# out_matrix.net
KiCad netlist of a schematic drawn in EAGLE
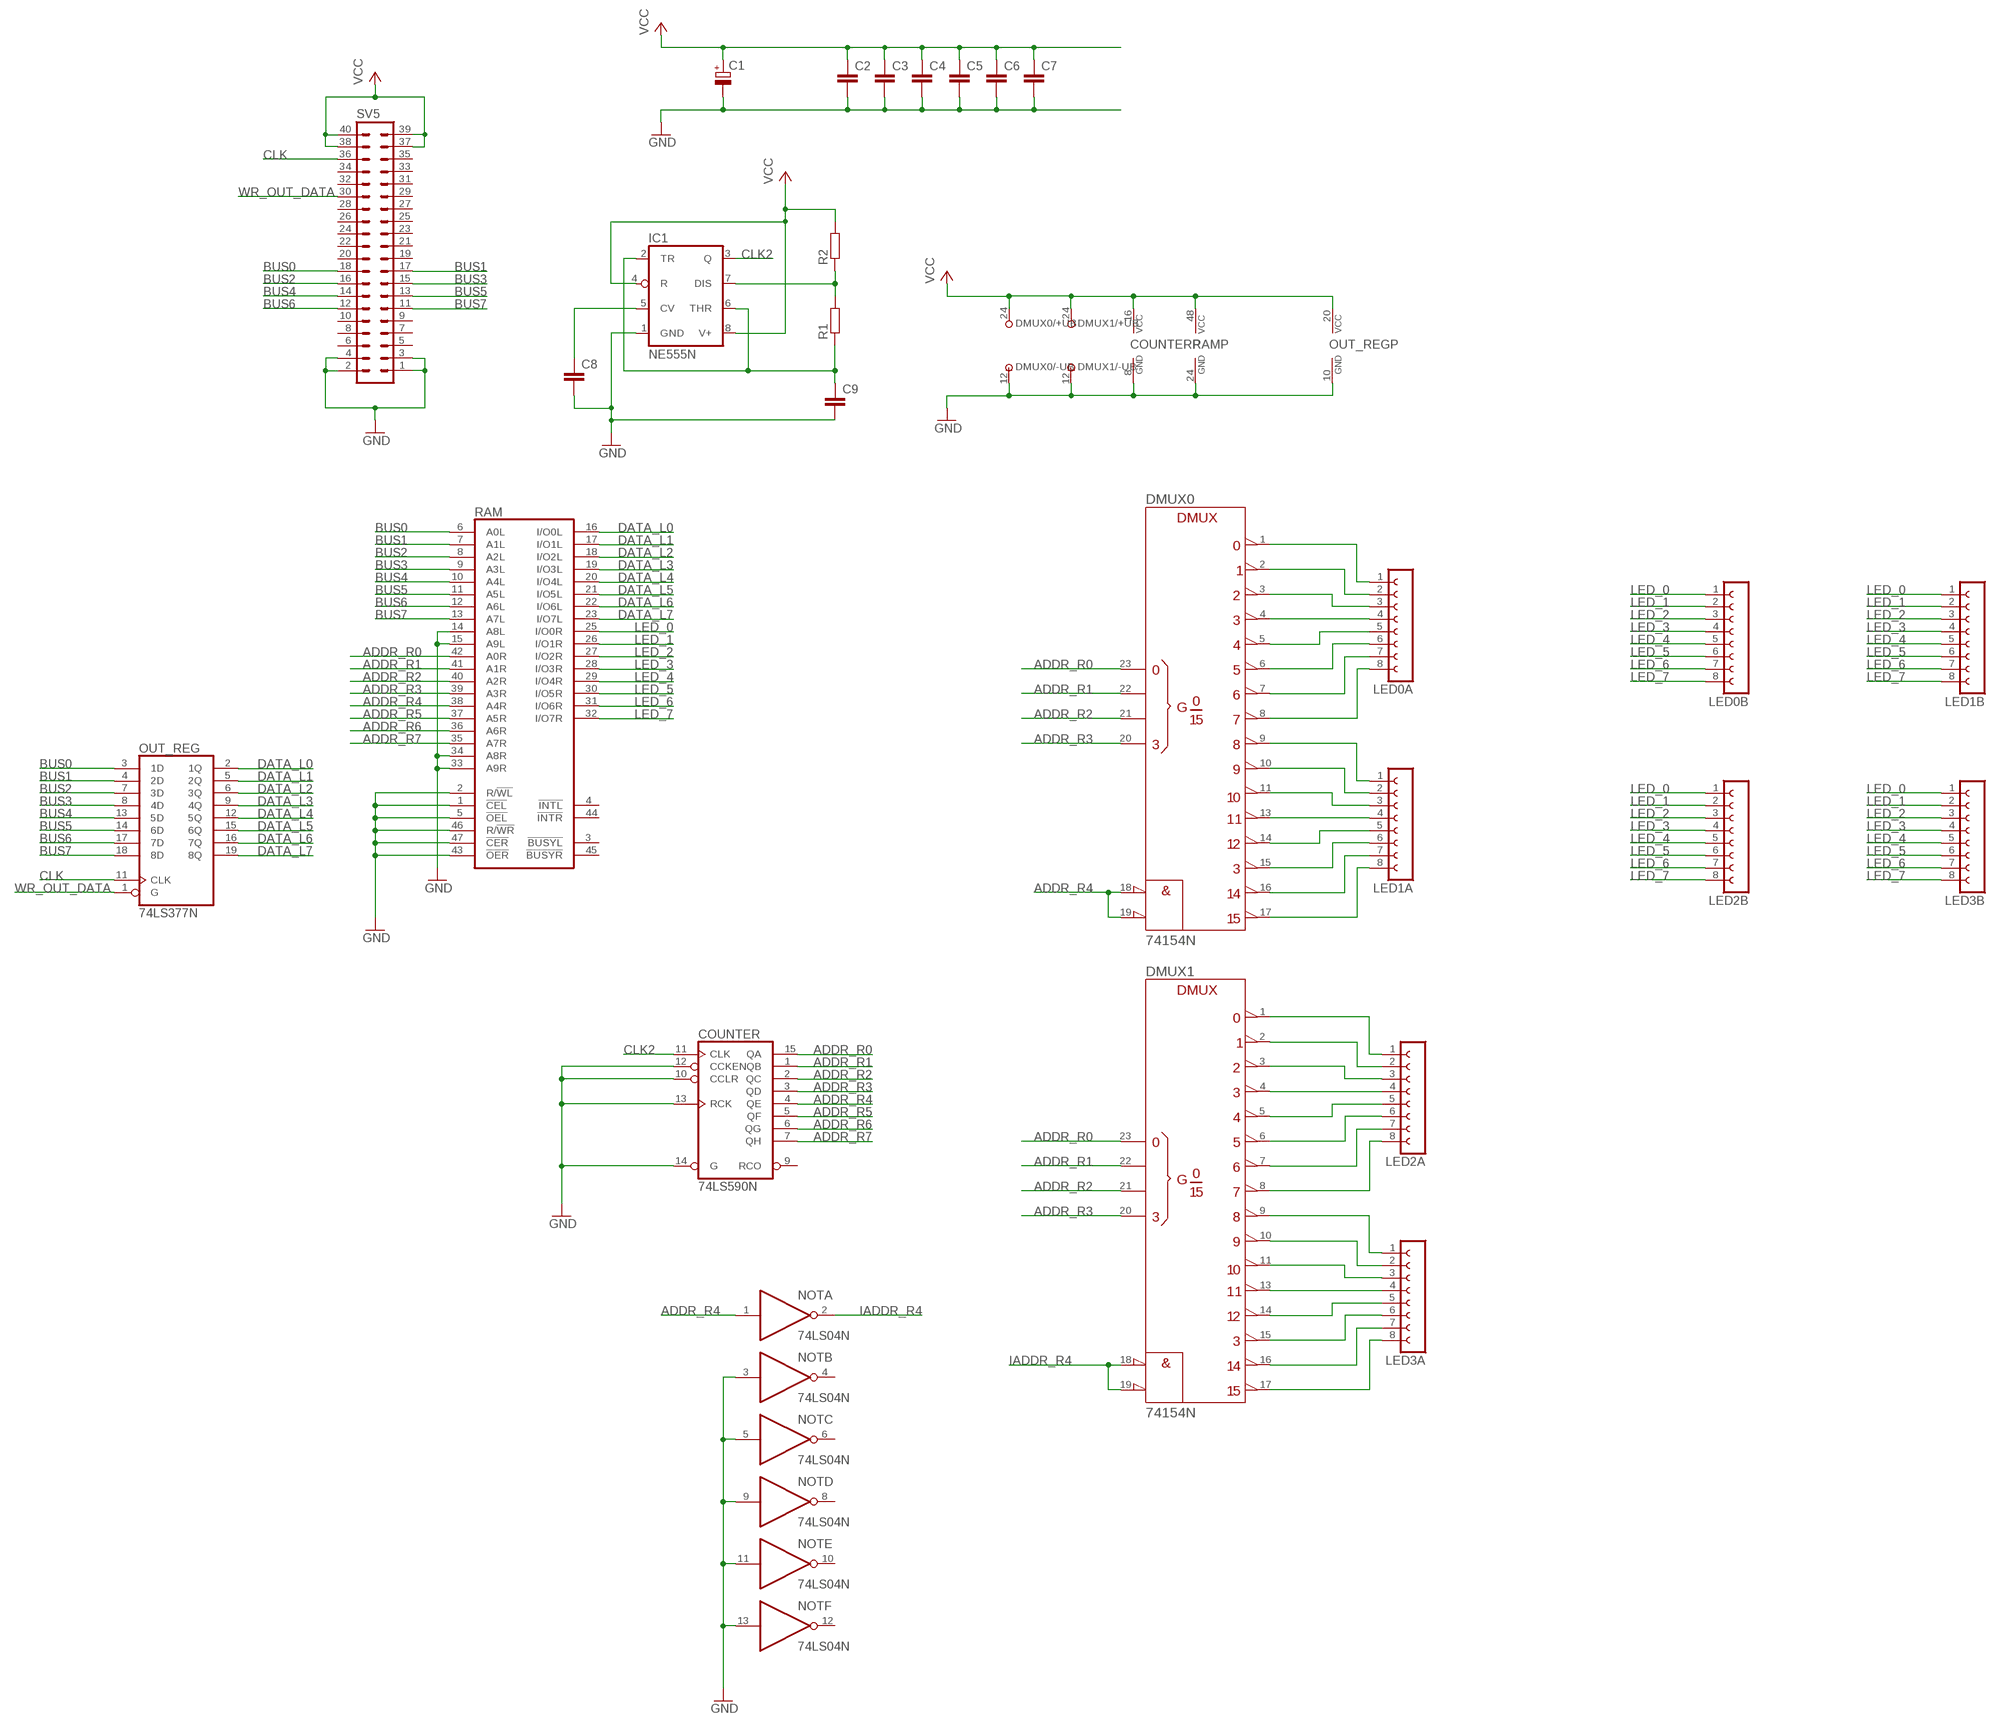
[diagram p0: schematic, sheet 1]

(export (version "E")
  (design (tool "Eeschema 10.0.6"))
  (components
    (comp (ref "C1")
      (value "CPOL-EUE3.5-8")
      (footprint "eagle-import:E3,5-8")
      (libsource (lib "eagle-import") (part "CPOL-EUE3.5-8"))
    )
    (comp (ref "C2")
      (value "C-EUC1206K")
      (footprint "eagle-import:C1206K")
      (libsource (lib "eagle-import") (part "C-EUC1206K"))
    )
    (comp (ref "C3")
      (value "C-EUC1206K")
      (footprint "eagle-import:C1206K")
      (libsource (lib "eagle-import") (part "C-EUC1206K"))
    )
    (comp (ref "C4")
      (value "C-EUC1206K")
      (footprint "eagle-import:C1206K")
      (libsource (lib "eagle-import") (part "C-EUC1206K"))
    )
    (comp (ref "C5")
      (value "C-EUC1206K")
      (footprint "eagle-import:C1206K")
      (libsource (lib "eagle-import") (part "C-EUC1206K"))
    )
    (comp (ref "C6")
      (value "C-EUC1206K")
      (footprint "eagle-import:C1206K")
      (libsource (lib "eagle-import") (part "C-EUC1206K"))
    )
    (comp (ref "C7")
      (value "C-EUC1206K")
      (footprint "eagle-import:C1206K")
      (libsource (lib "eagle-import") (part "C-EUC1206K"))
    )
    (comp (ref "C8")
      (value "C-EUC1206K")
      (footprint "eagle-import:C1206K")
      (libsource (lib "eagle-import") (part "C-EUC1206K"))
    )
    (comp (ref "C9")
      (value "C-EUC1206K")
      (footprint "eagle-import:C1206K")
      (libsource (lib "eagle-import") (part "C-EUC1206K"))
    )
    (comp (ref "COUNTER")
      (value "74LS590N")
      (footprint "eagle-import:DIL16")
      (libsource (lib "eagle-import") (part "74590NLS"))
    )
    (comp (ref "DMUX0")
      (value "74154N")
      (footprint "eagle-import:DIL24-3")
      (libsource (lib "eagle-import") (part "74154N"))
    )
    (comp (ref "DMUX1")
      (value "74154N")
      (footprint "eagle-import:DIL24-3")
      (libsource (lib "eagle-import") (part "74154N"))
    )
    (comp (ref "IC1")
      (value "NE555N")
      (footprint "eagle-import:DIL08")
      (libsource (lib "eagle-import") (part "555NNE"))
    )
    (comp (ref "LED0A")
      (value "FE08-1")
      (footprint "eagle-import:FE08")
      (libsource (lib "eagle-import") (part "FE08-1"))
    )
    (comp (ref "LED0B")
      (value "FE08-1")
      (footprint "eagle-import:FE08")
      (libsource (lib "eagle-import") (part "FE08-1"))
    )
    (comp (ref "LED1A")
      (value "FE08-1")
      (footprint "eagle-import:FE08")
      (libsource (lib "eagle-import") (part "FE08-1"))
    )
    (comp (ref "LED1B")
      (value "FE08-1")
      (footprint "eagle-import:FE08")
      (libsource (lib "eagle-import") (part "FE08-1"))
    )
    (comp (ref "LED2A")
      (value "FE08-1")
      (footprint "eagle-import:FE08")
      (libsource (lib "eagle-import") (part "FE08-1"))
    )
    (comp (ref "LED2B")
      (value "FE08-1")
      (footprint "eagle-import:FE08")
      (libsource (lib "eagle-import") (part "FE08-1"))
    )
    (comp (ref "LED3A")
      (value "FE08-1")
      (footprint "eagle-import:FE08")
      (libsource (lib "eagle-import") (part "FE08-1"))
    )
    (comp (ref "LED3B")
      (value "FE08-1")
      (footprint "eagle-import:FE08")
      (libsource (lib "eagle-import") (part "FE08-1"))
    )
    (comp (ref "NOT")
      (value "74LS04N")
      (footprint "eagle-import:DIL14")
      (libsource (lib "eagle-import") (part "7404NLS"))
    )
    (comp (ref "OUT_REG")
      (value "74LS377N")
      (footprint "eagle-import:DIL20")
      (libsource (lib "eagle-import") (part "74377NLS"))
    )
    (comp (ref "R1")
      (value "R-EU_M1206")
      (footprint "eagle-import:M1206")
      (libsource (lib "eagle-import") (part "R-EU_M1206"))
    )
    (comp (ref "R2")
      (value "R-EU_M1206")
      (footprint "eagle-import:M1206")
      (libsource (lib "eagle-import") (part "R-EU_M1206"))
    )
    (comp (ref "RAM")
      (value "7130P")
      (footprint "eagle-import:DIL48")
      (libsource (lib "eagle-import") (part "7130P"))
    )
    (comp (ref "SV5")
      (value "MA20-2W")
      (footprint "eagle-import:MA20-2W")
      (libsource (lib "eagle-import") (part "MA20-2W"))
    )
  )
  (nets
    (net (code "1") (name "/ADDR_R0") (class "Default")
      (node (ref "COUNTER") (pin "15") (pinfunction "QA_15") (pintype "tri_state"))
      (node (ref "DMUX0") (pin "23") (pinfunction "A_23") (pintype "input"))
      (node (ref "DMUX1") (pin "23") (pinfunction "A_23") (pintype "input"))
      (node (ref "RAM") (pin "42") (pinfunction "A0R_42") (pintype "input"))
    )
    (net (code "2") (name "/ADDR_R1") (class "Default")
      (node (ref "COUNTER") (pin "1") (pinfunction "QB_1") (pintype "tri_state"))
      (node (ref "DMUX0") (pin "22") (pinfunction "B_22") (pintype "input"))
      (node (ref "DMUX1") (pin "22") (pinfunction "B_22") (pintype "input"))
      (node (ref "RAM") (pin "41") (pinfunction "A1R_41") (pintype "input"))
    )
    (net (code "3") (name "/ADDR_R2") (class "Default")
      (node (ref "COUNTER") (pin "2") (pinfunction "QC_2") (pintype "tri_state"))
      (node (ref "DMUX0") (pin "21") (pinfunction "C_21") (pintype "input"))
      (node (ref "DMUX1") (pin "21") (pinfunction "C_21") (pintype "input"))
      (node (ref "RAM") (pin "40") (pinfunction "A2R_40") (pintype "input"))
    )
    (net (code "4") (name "/ADDR_R3") (class "Default")
      (node (ref "COUNTER") (pin "3") (pinfunction "QD_3") (pintype "tri_state"))
      (node (ref "DMUX0") (pin "20") (pinfunction "D_20") (pintype "input"))
      (node (ref "DMUX1") (pin "20") (pinfunction "D_20") (pintype "input"))
      (node (ref "RAM") (pin "39") (pinfunction "A3R_39") (pintype "input"))
    )
    (net (code "5") (name "/ADDR_R4") (class "Default")
      (node (ref "COUNTER") (pin "4") (pinfunction "QE_4") (pintype "tri_state"))
      (node (ref "DMUX0") (pin "18") (pinfunction "~{G1}_18") (pintype "input"))
      (node (ref "DMUX0") (pin "19") (pinfunction "~{G2}_19") (pintype "input"))
      (node (ref "NOT") (pin "1") (pinfunction "I_1") (pintype "input"))
      (node (ref "RAM") (pin "38") (pinfunction "A4R_38") (pintype "input"))
    )
    (net (code "6") (name "/ADDR_R5") (class "Default")
      (node (ref "COUNTER") (pin "5") (pinfunction "QF_5") (pintype "tri_state"))
      (node (ref "RAM") (pin "37") (pinfunction "A5R_37") (pintype "input"))
    )
    (net (code "7") (name "/ADDR_R6") (class "Default")
      (node (ref "COUNTER") (pin "6") (pinfunction "QG_6") (pintype "tri_state"))
      (node (ref "RAM") (pin "36") (pinfunction "A6R_36") (pintype "input"))
    )
    (net (code "8") (name "/ADDR_R7") (class "Default")
      (node (ref "COUNTER") (pin "7") (pinfunction "QH_7") (pintype "tri_state"))
      (node (ref "RAM") (pin "35") (pinfunction "A7R_35") (pintype "input"))
    )
    (net (code "9") (name "/BUS0") (class "Default")
      (node (ref "OUT_REG") (pin "3") (pinfunction "1D_3") (pintype "input"))
      (node (ref "RAM") (pin "6") (pinfunction "A0L_6") (pintype "input"))
      (node (ref "SV5") (pin "18") (pinfunction "18_18") (pintype "passive"))
    )
    (net (code "10") (name "/BUS1") (class "Default")
      (node (ref "OUT_REG") (pin "4") (pinfunction "2D_4") (pintype "input"))
      (node (ref "RAM") (pin "7") (pinfunction "A1L_7") (pintype "input"))
      (node (ref "SV5") (pin "17") (pinfunction "17_17") (pintype "passive"))
    )
    (net (code "11") (name "/BUS2") (class "Default")
      (node (ref "OUT_REG") (pin "7") (pinfunction "3D_7") (pintype "input"))
      (node (ref "RAM") (pin "8") (pinfunction "A2L_8") (pintype "input"))
      (node (ref "SV5") (pin "16") (pinfunction "16_16") (pintype "passive"))
    )
    (net (code "12") (name "/BUS3") (class "Default")
      (node (ref "OUT_REG") (pin "8") (pinfunction "4D_8") (pintype "input"))
      (node (ref "RAM") (pin "9") (pinfunction "A3L_9") (pintype "input"))
      (node (ref "SV5") (pin "15") (pinfunction "15_15") (pintype "passive"))
    )
    (net (code "13") (name "/BUS4") (class "Default")
      (node (ref "OUT_REG") (pin "13") (pinfunction "5D_13") (pintype "input"))
      (node (ref "RAM") (pin "10") (pinfunction "A4L_10") (pintype "input"))
      (node (ref "SV5") (pin "14") (pinfunction "14_14") (pintype "passive"))
    )
    (net (code "14") (name "/BUS5") (class "Default")
      (node (ref "OUT_REG") (pin "14") (pinfunction "6D_14") (pintype "input"))
      (node (ref "RAM") (pin "11") (pinfunction "A5L_11") (pintype "input"))
      (node (ref "SV5") (pin "13") (pinfunction "13_13") (pintype "passive"))
    )
    (net (code "15") (name "/BUS6") (class "Default")
      (node (ref "OUT_REG") (pin "17") (pinfunction "7D_17") (pintype "input"))
      (node (ref "RAM") (pin "12") (pinfunction "A6L_12") (pintype "input"))
      (node (ref "SV5") (pin "12") (pinfunction "12_12") (pintype "passive"))
    )
    (net (code "16") (name "/BUS7") (class "Default")
      (node (ref "OUT_REG") (pin "18") (pinfunction "8D_18") (pintype "input"))
      (node (ref "RAM") (pin "13") (pinfunction "A7L_13") (pintype "input"))
      (node (ref "SV5") (pin "11") (pinfunction "11_11") (pintype "passive"))
    )
    (net (code "17") (name "/CLK") (class "Default")
      (node (ref "OUT_REG") (pin "11") (pinfunction "CLK_11") (pintype "input"))
      (node (ref "SV5") (pin "36") (pinfunction "36_36") (pintype "passive"))
    )
    (net (code "18") (name "/CLK2") (class "Default")
      (node (ref "COUNTER") (pin "11") (pinfunction "CLK_11") (pintype "input"))
      (node (ref "IC1") (pin "3") (pinfunction "Q_3") (pintype "output"))
    )
    (net (code "19") (name "/DATA_L0") (class "Default")
      (node (ref "OUT_REG") (pin "2") (pinfunction "1Q_2") (pintype "output"))
      (node (ref "RAM") (pin "16") (pinfunction "I/O0L_16") (pintype "bidirectional"))
    )
    (net (code "20") (name "/DATA_L1") (class "Default")
      (node (ref "OUT_REG") (pin "5") (pinfunction "2Q_5") (pintype "output"))
      (node (ref "RAM") (pin "17") (pinfunction "I/O1L_17") (pintype "bidirectional"))
    )
    (net (code "21") (name "/DATA_L2") (class "Default")
      (node (ref "OUT_REG") (pin "6") (pinfunction "3Q_6") (pintype "output"))
      (node (ref "RAM") (pin "18") (pinfunction "I/O2L_18") (pintype "bidirectional"))
    )
    (net (code "22") (name "/DATA_L3") (class "Default")
      (node (ref "OUT_REG") (pin "9") (pinfunction "4Q_9") (pintype "output"))
      (node (ref "RAM") (pin "19") (pinfunction "I/O3L_19") (pintype "bidirectional"))
    )
    (net (code "23") (name "/DATA_L4") (class "Default")
      (node (ref "OUT_REG") (pin "12") (pinfunction "5Q_12") (pintype "output"))
      (node (ref "RAM") (pin "20") (pinfunction "I/O4L_20") (pintype "bidirectional"))
    )
    (net (code "24") (name "/DATA_L5") (class "Default")
      (node (ref "OUT_REG") (pin "15") (pinfunction "6Q_15") (pintype "output"))
      (node (ref "RAM") (pin "21") (pinfunction "I/O5L_21") (pintype "bidirectional"))
    )
    (net (code "25") (name "/DATA_L6") (class "Default")
      (node (ref "OUT_REG") (pin "16") (pinfunction "7Q_16") (pintype "output"))
      (node (ref "RAM") (pin "22") (pinfunction "I/O6L_22") (pintype "bidirectional"))
    )
    (net (code "26") (name "/DATA_L7") (class "Default")
      (node (ref "OUT_REG") (pin "19") (pinfunction "8Q_19") (pintype "output"))
      (node (ref "RAM") (pin "23") (pinfunction "I/O7L_23") (pintype "bidirectional"))
    )
    (net (code "27") (name "/IADDR_R4") (class "Default")
      (node (ref "DMUX1") (pin "18") (pinfunction "~{G1}_18") (pintype "input"))
      (node (ref "DMUX1") (pin "19") (pinfunction "~{G2}_19") (pintype "input"))
      (node (ref "NOT") (pin "2") (pinfunction "O_2") (pintype "output"))
    )
    (net (code "28") (name "/LED_0") (class "Default")
      (node (ref "LED0B") (pin "1") (pinfunction "1_1") (pintype "passive"))
      (node (ref "LED1B") (pin "1") (pinfunction "1_1") (pintype "passive"))
      (node (ref "LED2B") (pin "1") (pinfunction "1_1") (pintype "passive"))
      (node (ref "LED3B") (pin "1") (pinfunction "1_1") (pintype "passive"))
      (node (ref "RAM") (pin "25") (pinfunction "I/O0R_25") (pintype "bidirectional"))
    )
    (net (code "29") (name "/LED_1") (class "Default")
      (node (ref "LED0B") (pin "2") (pinfunction "2_2") (pintype "passive"))
      (node (ref "LED1B") (pin "2") (pinfunction "2_2") (pintype "passive"))
      (node (ref "LED2B") (pin "2") (pinfunction "2_2") (pintype "passive"))
      (node (ref "LED3B") (pin "2") (pinfunction "2_2") (pintype "passive"))
      (node (ref "RAM") (pin "26") (pinfunction "I/O1R_26") (pintype "bidirectional"))
    )
    (net (code "30") (name "/LED_2") (class "Default")
      (node (ref "LED0B") (pin "3") (pinfunction "3_3") (pintype "passive"))
      (node (ref "LED1B") (pin "3") (pinfunction "3_3") (pintype "passive"))
      (node (ref "LED2B") (pin "3") (pinfunction "3_3") (pintype "passive"))
      (node (ref "LED3B") (pin "3") (pinfunction "3_3") (pintype "passive"))
      (node (ref "RAM") (pin "27") (pinfunction "I/O2R_27") (pintype "bidirectional"))
    )
    (net (code "31") (name "/LED_3") (class "Default")
      (node (ref "LED0B") (pin "4") (pinfunction "4_4") (pintype "passive"))
      (node (ref "LED1B") (pin "4") (pinfunction "4_4") (pintype "passive"))
      (node (ref "LED2B") (pin "4") (pinfunction "4_4") (pintype "passive"))
      (node (ref "LED3B") (pin "4") (pinfunction "4_4") (pintype "passive"))
      (node (ref "RAM") (pin "28") (pinfunction "I/O3R_28") (pintype "bidirectional"))
    )
    (net (code "32") (name "/LED_4") (class "Default")
      (node (ref "LED0B") (pin "5") (pinfunction "5_5") (pintype "passive"))
      (node (ref "LED1B") (pin "5") (pinfunction "5_5") (pintype "passive"))
      (node (ref "LED2B") (pin "5") (pinfunction "5_5") (pintype "passive"))
      (node (ref "LED3B") (pin "5") (pinfunction "5_5") (pintype "passive"))
      (node (ref "RAM") (pin "29") (pinfunction "I/O4R_29") (pintype "bidirectional"))
    )
    (net (code "33") (name "/LED_5") (class "Default")
      (node (ref "LED0B") (pin "6") (pinfunction "6_6") (pintype "passive"))
      (node (ref "LED1B") (pin "6") (pinfunction "6_6") (pintype "passive"))
      (node (ref "LED2B") (pin "6") (pinfunction "6_6") (pintype "passive"))
      (node (ref "LED3B") (pin "6") (pinfunction "6_6") (pintype "passive"))
      (node (ref "RAM") (pin "30") (pinfunction "I/O5R_30") (pintype "bidirectional"))
    )
    (net (code "34") (name "/LED_6") (class "Default")
      (node (ref "LED0B") (pin "7") (pinfunction "7_7") (pintype "passive"))
      (node (ref "LED1B") (pin "7") (pinfunction "7_7") (pintype "passive"))
      (node (ref "LED2B") (pin "7") (pinfunction "7_7") (pintype "passive"))
      (node (ref "LED3B") (pin "7") (pinfunction "7_7") (pintype "passive"))
      (node (ref "RAM") (pin "31") (pinfunction "I/O6R_31") (pintype "bidirectional"))
    )
    (net (code "35") (name "/LED_7") (class "Default")
      (node (ref "LED0B") (pin "8") (pinfunction "8_8") (pintype "passive"))
      (node (ref "LED1B") (pin "8") (pinfunction "8_8") (pintype "passive"))
      (node (ref "LED2B") (pin "8") (pinfunction "8_8") (pintype "passive"))
      (node (ref "LED3B") (pin "8") (pinfunction "8_8") (pintype "passive"))
      (node (ref "RAM") (pin "32") (pinfunction "I/O7R_32") (pintype "bidirectional"))
    )
    (net (code "36") (name "/WR_OUT_DATA") (class "Default")
      (node (ref "OUT_REG") (pin "1") (pinfunction "G_1") (pintype "input"))
      (node (ref "SV5") (pin "30") (pinfunction "30_30") (pintype "passive"))
    )
    (net (code "37") (name "GND") (class "Default")
      (node (ref "C1") (pin "-") (pinfunction "-_-") (pintype "passive"))
      (node (ref "C2") (pin "2") (pinfunction "2_2") (pintype "passive"))
      (node (ref "C3") (pin "2") (pinfunction "2_2") (pintype "passive"))
      (node (ref "C4") (pin "2") (pinfunction "2_2") (pintype "passive"))
      (node (ref "C5") (pin "2") (pinfunction "2_2") (pintype "passive"))
      (node (ref "C6") (pin "2") (pinfunction "2_2") (pintype "passive"))
      (node (ref "C7") (pin "2") (pinfunction "2_2") (pintype "passive"))
      (node (ref "C8") (pin "2") (pinfunction "2_2") (pintype "passive"))
      (node (ref "C9") (pin "2") (pinfunction "2_2") (pintype "passive"))
      (node (ref "COUNTER") (pin "10") (pinfunction "CCLR_10") (pintype "input"))
      (node (ref "COUNTER") (pin "12") (pinfunction "CCKEN_12") (pintype "input"))
      (node (ref "COUNTER") (pin "13") (pinfunction "RCK_13") (pintype "input"))
      (node (ref "COUNTER") (pin "14") (pinfunction "G_14") (pintype "input"))
      (node (ref "COUNTER") (pin "8") (pinfunction "GND_8") (pintype "power_in"))
      (node (ref "DMUX0") (pin "12") (pinfunction "-UB_12") (pintype "power_in"))
      (node (ref "DMUX1") (pin "12") (pinfunction "-UB_12") (pintype "power_in"))
      (node (ref "IC1") (pin "1") (pinfunction "GND_1") (pintype "power_in"))
      (node (ref "NOT") (pin "11") (pinfunction "I_11") (pintype "input"))
      (node (ref "NOT") (pin "13") (pinfunction "I_13") (pintype "input"))
      (node (ref "NOT") (pin "3") (pinfunction "I_3") (pintype "input"))
      (node (ref "NOT") (pin "5") (pinfunction "I_5") (pintype "input"))
      (node (ref "NOT") (pin "9") (pinfunction "I_9") (pintype "input"))
      (node (ref "OUT_REG") (pin "10") (pinfunction "GND_10") (pintype "power_in"))
      (node (ref "RAM") (pin "1") (pinfunction "~{CEL}_1") (pintype "input"))
      (node (ref "RAM") (pin "14") (pinfunction "A8L_14") (pintype "input"))
      (node (ref "RAM") (pin "15") (pinfunction "A9L_15") (pintype "input"))
      (node (ref "RAM") (pin "2") (pinfunction "R/~{WL}_2") (pintype "input"))
      (node (ref "RAM") (pin "24") (pinfunction "GND_24") (pintype "power_in"))
      (node (ref "RAM") (pin "33") (pinfunction "A9R_33") (pintype "input"))
      (node (ref "RAM") (pin "34") (pinfunction "A8R_34") (pintype "input"))
      (node (ref "RAM") (pin "43") (pinfunction "~{OER}_43") (pintype "input"))
      (node (ref "RAM") (pin "46") (pinfunction "R/~{WR}_46") (pintype "input"))
      (node (ref "RAM") (pin "47") (pinfunction "~{CER}_47") (pintype "input"))
      (node (ref "RAM") (pin "5") (pinfunction "~{OEL}_5") (pintype "input"))
      (node (ref "SV5") (pin "1") (pinfunction "1_1") (pintype "passive"))
      (node (ref "SV5") (pin "2") (pinfunction "2_2") (pintype "passive"))
      (node (ref "SV5") (pin "3") (pinfunction "3_3") (pintype "passive"))
      (node (ref "SV5") (pin "4") (pinfunction "4_4") (pintype "passive"))
    )
    (net (code "38") (name "Net-(DMUX0C-0)") (class "Default")
      (node (ref "DMUX0") (pin "1") (pinfunction "0_1") (pintype "output"))
      (node (ref "LED0A") (pin "1") (pinfunction "1_1") (pintype "passive"))
    )
    (net (code "39") (name "Net-(DMUX0C-1)") (class "Default")
      (node (ref "DMUX0") (pin "2") (pinfunction "1_2") (pintype "output"))
      (node (ref "LED0A") (pin "2") (pinfunction "2_2") (pintype "passive"))
    )
    (net (code "40") (name "Net-(DMUX0C-2)") (class "Default")
      (node (ref "DMUX0") (pin "3") (pinfunction "2_3") (pintype "output"))
      (node (ref "LED0A") (pin "3") (pinfunction "3_3") (pintype "passive"))
    )
    (net (code "41") (name "Net-(DMUX0C-3)") (class "Default")
      (node (ref "DMUX0") (pin "4") (pinfunction "3_4") (pintype "output"))
      (node (ref "LED0A") (pin "4") (pinfunction "4_4") (pintype "passive"))
    )
    (net (code "42") (name "Net-(DMUX0C-4)") (class "Default")
      (node (ref "DMUX0") (pin "5") (pinfunction "4_5") (pintype "output"))
      (node (ref "LED0A") (pin "5") (pinfunction "5_5") (pintype "passive"))
    )
    (net (code "43") (name "Net-(DMUX0C-5)") (class "Default")
      (node (ref "DMUX0") (pin "6") (pinfunction "5_6") (pintype "output"))
      (node (ref "LED0A") (pin "6") (pinfunction "6_6") (pintype "passive"))
    )
    (net (code "44") (name "Net-(DMUX0C-6)") (class "Default")
      (node (ref "DMUX0") (pin "7") (pinfunction "6_7") (pintype "output"))
      (node (ref "LED0A") (pin "7") (pinfunction "7_7") (pintype "passive"))
    )
    (net (code "45") (name "Net-(DMUX0C-7)") (class "Default")
      (node (ref "DMUX0") (pin "8") (pinfunction "7_8") (pintype "output"))
      (node (ref "LED0A") (pin "8") (pinfunction "8_8") (pintype "passive"))
    )
    (net (code "46") (name "Net-(DMUX0C-8)") (class "Default")
      (node (ref "DMUX0") (pin "9") (pinfunction "8_9") (pintype "output"))
      (node (ref "LED1A") (pin "1") (pinfunction "1_1") (pintype "passive"))
    )
    (net (code "47") (name "Net-(DMUX0C-9)") (class "Default")
      (node (ref "DMUX0") (pin "10") (pinfunction "9_10") (pintype "output"))
      (node (ref "LED1A") (pin "2") (pinfunction "2_2") (pintype "passive"))
    )
    (net (code "48") (name "Net-(DMUX0C-10)") (class "Default")
      (node (ref "DMUX0") (pin "11") (pinfunction "10_11") (pintype "output"))
      (node (ref "LED1A") (pin "3") (pinfunction "3_3") (pintype "passive"))
    )
    (net (code "49") (name "Net-(DMUX0C-11)") (class "Default")
      (node (ref "DMUX0") (pin "13") (pinfunction "11_13") (pintype "output"))
      (node (ref "LED1A") (pin "4") (pinfunction "4_4") (pintype "passive"))
    )
    (net (code "50") (name "Net-(DMUX0C-12)") (class "Default")
      (node (ref "DMUX0") (pin "14") (pinfunction "12_14") (pintype "output"))
      (node (ref "LED1A") (pin "5") (pinfunction "5_5") (pintype "passive"))
    )
    (net (code "51") (name "Net-(DMUX0C-13)") (class "Default")
      (node (ref "DMUX0") (pin "15") (pinfunction "13_15") (pintype "output"))
      (node (ref "LED1A") (pin "6") (pinfunction "6_6") (pintype "passive"))
    )
    (net (code "52") (name "Net-(DMUX0C-14)") (class "Default")
      (node (ref "DMUX0") (pin "16") (pinfunction "14_16") (pintype "output"))
      (node (ref "LED1A") (pin "7") (pinfunction "7_7") (pintype "passive"))
    )
    (net (code "53") (name "Net-(DMUX0C-15)") (class "Default")
      (node (ref "DMUX0") (pin "17") (pinfunction "15_17") (pintype "output"))
      (node (ref "LED1A") (pin "8") (pinfunction "8_8") (pintype "passive"))
    )
    (net (code "54") (name "Net-(DMUX1C-0)") (class "Default")
      (node (ref "DMUX1") (pin "1") (pinfunction "0_1") (pintype "output"))
      (node (ref "LED2A") (pin "1") (pinfunction "1_1") (pintype "passive"))
    )
    (net (code "55") (name "Net-(DMUX1C-1)") (class "Default")
      (node (ref "DMUX1") (pin "2") (pinfunction "1_2") (pintype "output"))
      (node (ref "LED2A") (pin "2") (pinfunction "2_2") (pintype "passive"))
    )
    (net (code "56") (name "Net-(DMUX1C-2)") (class "Default")
      (node (ref "DMUX1") (pin "3") (pinfunction "2_3") (pintype "output"))
      (node (ref "LED2A") (pin "3") (pinfunction "3_3") (pintype "passive"))
    )
    (net (code "57") (name "Net-(DMUX1C-3)") (class "Default")
      (node (ref "DMUX1") (pin "4") (pinfunction "3_4") (pintype "output"))
      (node (ref "LED2A") (pin "4") (pinfunction "4_4") (pintype "passive"))
    )
    (net (code "58") (name "Net-(DMUX1C-4)") (class "Default")
      (node (ref "DMUX1") (pin "5") (pinfunction "4_5") (pintype "output"))
      (node (ref "LED2A") (pin "5") (pinfunction "5_5") (pintype "passive"))
    )
    (net (code "59") (name "Net-(DMUX1C-5)") (class "Default")
      (node (ref "DMUX1") (pin "6") (pinfunction "5_6") (pintype "output"))
      (node (ref "LED2A") (pin "6") (pinfunction "6_6") (pintype "passive"))
    )
    (net (code "60") (name "Net-(DMUX1C-6)") (class "Default")
      (node (ref "DMUX1") (pin "7") (pinfunction "6_7") (pintype "output"))
      (node (ref "LED2A") (pin "7") (pinfunction "7_7") (pintype "passive"))
    )
    (net (code "61") (name "Net-(DMUX1C-7)") (class "Default")
      (node (ref "DMUX1") (pin "8") (pinfunction "7_8") (pintype "output"))
      (node (ref "LED2A") (pin "8") (pinfunction "8_8") (pintype "passive"))
    )
    (net (code "62") (name "Net-(DMUX1C-8)") (class "Default")
      (node (ref "DMUX1") (pin "9") (pinfunction "8_9") (pintype "output"))
      (node (ref "LED3A") (pin "1") (pinfunction "1_1") (pintype "passive"))
    )
    (net (code "63") (name "Net-(DMUX1C-9)") (class "Default")
      (node (ref "DMUX1") (pin "10") (pinfunction "9_10") (pintype "output"))
      (node (ref "LED3A") (pin "2") (pinfunction "2_2") (pintype "passive"))
    )
    (net (code "64") (name "Net-(DMUX1C-10)") (class "Default")
      (node (ref "DMUX1") (pin "11") (pinfunction "10_11") (pintype "output"))
      (node (ref "LED3A") (pin "3") (pinfunction "3_3") (pintype "passive"))
    )
    (net (code "65") (name "Net-(DMUX1C-11)") (class "Default")
      (node (ref "DMUX1") (pin "13") (pinfunction "11_13") (pintype "output"))
      (node (ref "LED3A") (pin "4") (pinfunction "4_4") (pintype "passive"))
    )
    (net (code "66") (name "Net-(DMUX1C-12)") (class "Default")
      (node (ref "DMUX1") (pin "14") (pinfunction "12_14") (pintype "output"))
      (node (ref "LED3A") (pin "5") (pinfunction "5_5") (pintype "passive"))
    )
    (net (code "67") (name "Net-(DMUX1C-13)") (class "Default")
      (node (ref "DMUX1") (pin "15") (pinfunction "13_15") (pintype "output"))
      (node (ref "LED3A") (pin "6") (pinfunction "6_6") (pintype "passive"))
    )
    (net (code "68") (name "Net-(DMUX1C-14)") (class "Default")
      (node (ref "DMUX1") (pin "16") (pinfunction "14_16") (pintype "output"))
      (node (ref "LED3A") (pin "7") (pinfunction "7_7") (pintype "passive"))
    )
    (net (code "69") (name "Net-(DMUX1C-15)") (class "Default")
      (node (ref "DMUX1") (pin "17") (pinfunction "15_17") (pintype "output"))
      (node (ref "LED3A") (pin "8") (pinfunction "8_8") (pintype "passive"))
    )
    (net (code "70") (name "Net-(IC1-CV)") (class "Default")
      (node (ref "C8") (pin "1") (pinfunction "1_1") (pintype "passive"))
      (node (ref "IC1") (pin "5") (pinfunction "CV_5") (pintype "input"))
    )
    (net (code "71") (name "Net-(IC1-DIS)") (class "Default")
      (node (ref "IC1") (pin "7") (pinfunction "DIS_7") (pintype "input"))
      (node (ref "R1") (pin "2") (pinfunction "2_2") (pintype "passive"))
      (node (ref "R2") (pin "1") (pinfunction "1_1") (pintype "passive"))
    )
    (net (code "72") (name "Net-(IC1-THR)") (class "Default")
      (node (ref "C9") (pin "1") (pinfunction "1_1") (pintype "passive"))
      (node (ref "IC1") (pin "2") (pinfunction "TR_2") (pintype "input"))
      (node (ref "IC1") (pin "6") (pinfunction "THR_6") (pintype "input"))
      (node (ref "R1") (pin "1") (pinfunction "1_1") (pintype "passive"))
    )
    (net (code "73") (name "VCC") (class "Default")
      (node (ref "C1") (pin "+") (pinfunction "+_+") (pintype "passive"))
      (node (ref "C2") (pin "1") (pinfunction "1_1") (pintype "passive"))
      (node (ref "C3") (pin "1") (pinfunction "1_1") (pintype "passive"))
      (node (ref "C4") (pin "1") (pinfunction "1_1") (pintype "passive"))
      (node (ref "C5") (pin "1") (pinfunction "1_1") (pintype "passive"))
      (node (ref "C6") (pin "1") (pinfunction "1_1") (pintype "passive"))
      (node (ref "C7") (pin "1") (pinfunction "1_1") (pintype "passive"))
      (node (ref "COUNTER") (pin "16") (pinfunction "VCC_16") (pintype "power_in"))
      (node (ref "DMUX0") (pin "24") (pinfunction "+UB_24") (pintype "power_in"))
      (node (ref "DMUX1") (pin "24") (pinfunction "+UB_24") (pintype "power_in"))
      (node (ref "IC1") (pin "4") (pinfunction "R_4") (pintype "input"))
      (node (ref "IC1") (pin "8") (pinfunction "V+_8") (pintype "power_in"))
      (node (ref "OUT_REG") (pin "20") (pinfunction "VCC_20") (pintype "power_in"))
      (node (ref "R2") (pin "2") (pinfunction "2_2") (pintype "passive"))
      (node (ref "RAM") (pin "48") (pinfunction "VCC_48") (pintype "power_in"))
      (node (ref "SV5") (pin "37") (pinfunction "37_37") (pintype "passive"))
      (node (ref "SV5") (pin "38") (pinfunction "38_38") (pintype "passive"))
      (node (ref "SV5") (pin "39") (pinfunction "39_39") (pintype "passive"))
      (node (ref "SV5") (pin "40") (pinfunction "40_40") (pintype "passive"))
    )
    (net (code "74") (name "unconnected-(COUNTERA-RCO-Pad9)") (class "Default")
      (node (ref "COUNTER") (pin "9") (pinfunction "RCO_9") (pintype "output"))
    )
    (net (code "75") (name "unconnected-(NOTB-O-Pad4)") (class "Default")
      (node (ref "NOT") (pin "4") (pinfunction "O_4") (pintype "output"))
    )
    (net (code "76") (name "unconnected-(NOTC-O-Pad6)") (class "Default")
      (node (ref "NOT") (pin "6") (pinfunction "O_6") (pintype "output"))
    )
    (net (code "77") (name "unconnected-(NOTD-O-Pad8)") (class "Default")
      (node (ref "NOT") (pin "8") (pinfunction "O_8") (pintype "output"))
    )
    (net (code "78") (name "unconnected-(NOTE-O-Pad10)") (class "Default")
      (node (ref "NOT") (pin "10") (pinfunction "O_10") (pintype "output"))
    )
    (net (code "79") (name "unconnected-(NOTF-O-Pad12)") (class "Default")
      (node (ref "NOT") (pin "12") (pinfunction "O_12") (pintype "output"))
    )
    (net (code "80") (name "unconnected-(RAMA-~{BUSYL}-Pad3)") (class "Default")
      (node (ref "RAM") (pin "3") (pinfunction "~{BUSYL}_3") (pintype "bidirectional"))
    )
    (net (code "81") (name "unconnected-(RAMA-~{BUSYR}-Pad45)") (class "Default")
      (node (ref "RAM") (pin "45") (pinfunction "~{BUSYR}_45") (pintype "bidirectional"))
    )
    (net (code "82") (name "unconnected-(RAMA-~{INTL}-Pad4)") (class "Default")
      (node (ref "RAM") (pin "4") (pinfunction "~{INTL}_4") (pintype "output"))
    )
    (net (code "83") (name "unconnected-(RAMA-~{INTR}-Pad44)") (class "Default")
      (node (ref "RAM") (pin "44") (pinfunction "~{INTR}_44") (pintype "output"))
    )
    (net (code "84") (name "unconnected-(SV5-Pad5)") (class "Default")
      (node (ref "SV5") (pin "5") (pinfunction "5_5") (pintype "passive"))
    )
    (net (code "85") (name "unconnected-(SV5-Pad6)") (class "Default")
      (node (ref "SV5") (pin "6") (pinfunction "6_6") (pintype "passive"))
    )
    (net (code "86") (name "unconnected-(SV5-Pad7)") (class "Default")
      (node (ref "SV5") (pin "7") (pinfunction "7_7") (pintype "passive"))
    )
    (net (code "87") (name "unconnected-(SV5-Pad8)") (class "Default")
      (node (ref "SV5") (pin "8") (pinfunction "8_8") (pintype "passive"))
    )
    (net (code "88") (name "unconnected-(SV5-Pad9)") (class "Default")
      (node (ref "SV5") (pin "9") (pinfunction "9_9") (pintype "passive"))
    )
    (net (code "89") (name "unconnected-(SV5-Pad10)") (class "Default")
      (node (ref "SV5") (pin "10") (pinfunction "10_10") (pintype "passive"))
    )
    (net (code "90") (name "unconnected-(SV5-Pad19)") (class "Default")
      (node (ref "SV5") (pin "19") (pinfunction "19_19") (pintype "passive"))
    )
    (net (code "91") (name "unconnected-(SV5-Pad20)") (class "Default")
      (node (ref "SV5") (pin "20") (pinfunction "20_20") (pintype "passive"))
    )
    (net (code "92") (name "unconnected-(SV5-Pad21)") (class "Default")
      (node (ref "SV5") (pin "21") (pinfunction "21_21") (pintype "passive"))
    )
    (net (code "93") (name "unconnected-(SV5-Pad22)") (class "Default")
      (node (ref "SV5") (pin "22") (pinfunction "22_22") (pintype "passive"))
    )
    (net (code "94") (name "unconnected-(SV5-Pad23)") (class "Default")
      (node (ref "SV5") (pin "23") (pinfunction "23_23") (pintype "passive"))
    )
    (net (code "95") (name "unconnected-(SV5-Pad24)") (class "Default")
      (node (ref "SV5") (pin "24") (pinfunction "24_24") (pintype "passive"))
    )
    (net (code "96") (name "unconnected-(SV5-Pad25)") (class "Default")
      (node (ref "SV5") (pin "25") (pinfunction "25_25") (pintype "passive"))
    )
    (net (code "97") (name "unconnected-(SV5-Pad26)") (class "Default")
      (node (ref "SV5") (pin "26") (pinfunction "26_26") (pintype "passive"))
    )
    (net (code "98") (name "unconnected-(SV5-Pad27)") (class "Default")
      (node (ref "SV5") (pin "27") (pinfunction "27_27") (pintype "passive"))
    )
    (net (code "99") (name "unconnected-(SV5-Pad28)") (class "Default")
      (node (ref "SV5") (pin "28") (pinfunction "28_28") (pintype "passive"))
    )
    (net (code "100") (name "unconnected-(SV5-Pad29)") (class "Default")
      (node (ref "SV5") (pin "29") (pinfunction "29_29") (pintype "passive"))
    )
    (net (code "101") (name "unconnected-(SV5-Pad31)") (class "Default")
      (node (ref "SV5") (pin "31") (pinfunction "31_31") (pintype "passive"))
    )
    (net (code "102") (name "unconnected-(SV5-Pad32)") (class "Default")
      (node (ref "SV5") (pin "32") (pinfunction "32_32") (pintype "passive"))
    )
    (net (code "103") (name "unconnected-(SV5-Pad33)") (class "Default")
      (node (ref "SV5") (pin "33") (pinfunction "33_33") (pintype "passive"))
    )
    (net (code "104") (name "unconnected-(SV5-Pad34)") (class "Default")
      (node (ref "SV5") (pin "34") (pinfunction "34_34") (pintype "passive"))
    )
    (net (code "105") (name "unconnected-(SV5-Pad35)") (class "Default")
      (node (ref "SV5") (pin "35") (pinfunction "35_35") (pintype "passive"))
    )
  )
)
